# D3R900.net
KiCad netlist of a schematic drawn in Altium Designer
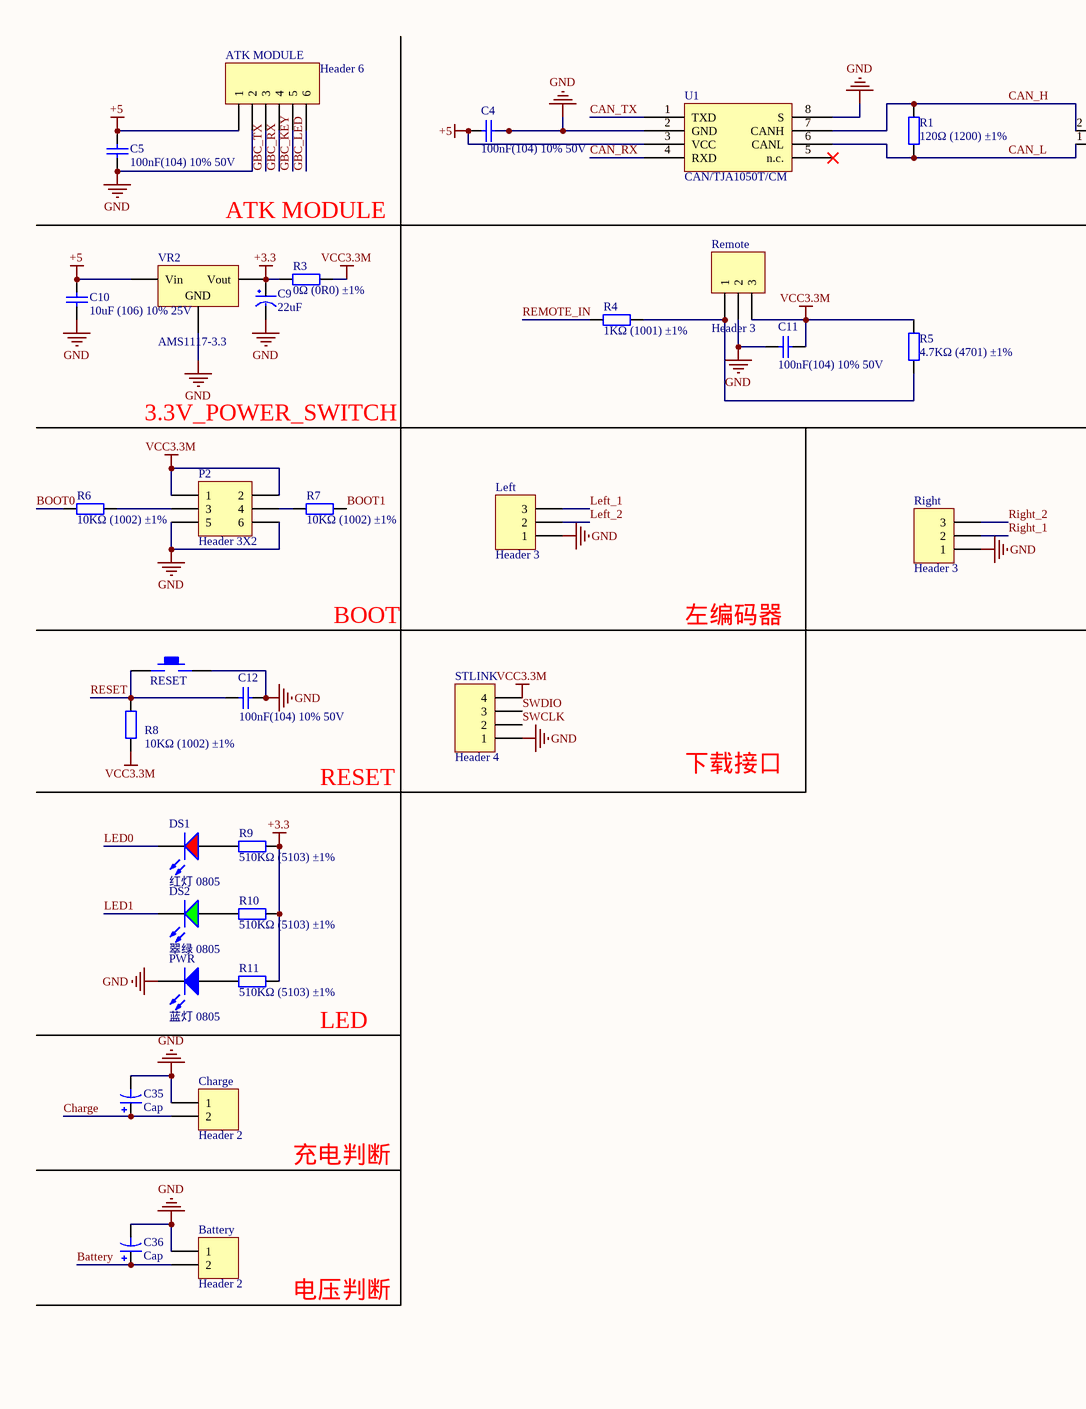
[diagram p0: D3R900.SchDoc, left]
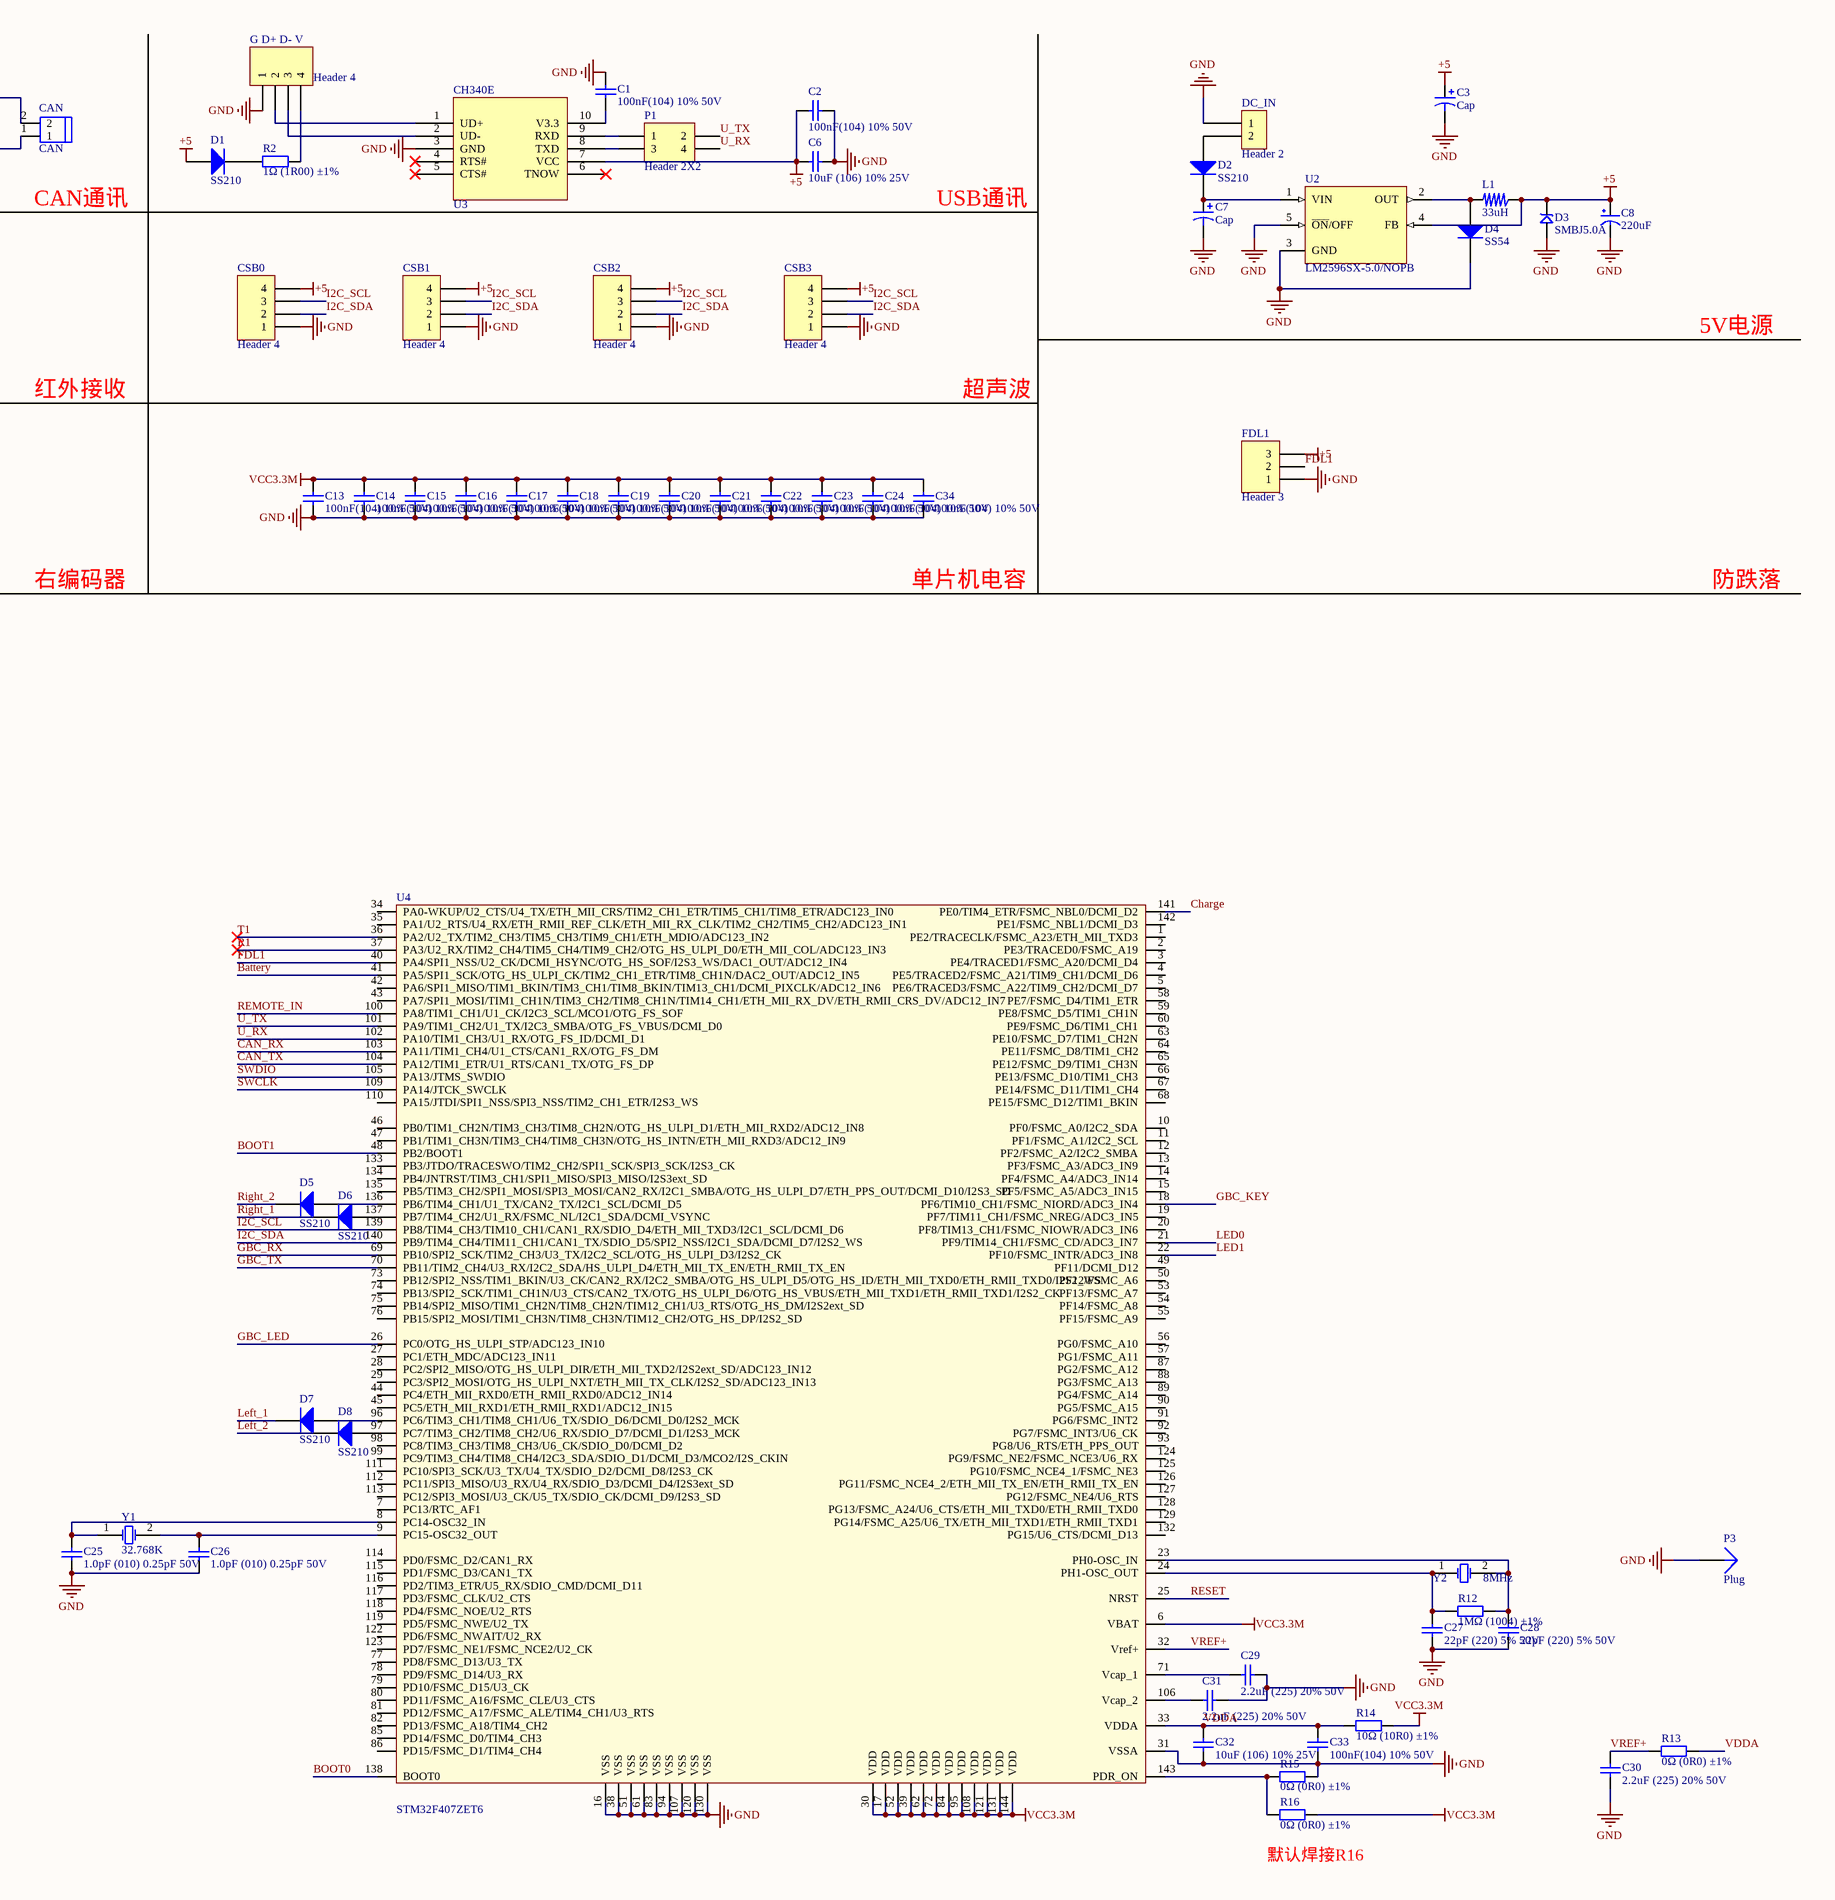
[diagram p1: D3R900.SchDoc, right]

(export (version "E")
  (design (tool "Eeschema 10.0.6"))
  (components
    (comp (ref "ATK MODULE")
      (value "Header 6")
      (footprint "HDR1X6")
      (description "Header, 6-Pin")
      (fields (field (name "PUBLISHER") "Altium Limited"))
      (libsource (lib "Miscellaneous Connectors") (part "Header 6"))
    )
    (comp (ref "Battery")
      (value "Header 2")
      (footprint "HDR1X2")
      (description "Header, 2-Pin")
      (fields (field (name "PUBLISHER") "Altium Limited"))
      (libsource (lib "Miscellaneous Connectors") (part "Header 2"))
    )
    (comp (ref "C1")
      (value "100nF(104) 10% 50V")
      (footprint "LC-0805_C")
      (description "贴片电容")
      (libsource (lib "Miscellaneous Devices LC") (part "0805 100nF(104) 10% 50V"))
    )
    (comp (ref "C2")
      (value "100nF(104) 10% 50V")
      (footprint "LC-0805_C")
      (description "贴片电容")
      (libsource (lib "Miscellaneous Devices LC") (part "0805 100nF(104) 10% 50V"))
    )
    (comp (ref "C3")
      (value "Cap")
      (footprint "CAP-DIP-3.5")
      (description "Cap_DIP")
      (libsource (lib "AD_Chip_Y") (part "Cap_DIP"))
    )
    (comp (ref "C4")
      (value "100nF(104) 10% 50V")
      (footprint "LC-0805_C")
      (description "贴片电容")
      (libsource (lib "Miscellaneous Devices LC") (part "0805 100nF(104) 10% 50V"))
    )
    (comp (ref "C5")
      (value "100nF(104) 10% 50V")
      (footprint "LC-0805_C")
      (description "贴片电容")
      (libsource (lib "Miscellaneous Devices LC") (part "0805 100nF(104) 10% 50V"))
    )
    (comp (ref "C6")
      (value "10uF (106) 10% 25V")
      (footprint "LC-0805_C")
      (description "贴片电容")
      (libsource (lib "Miscellaneous Devices LC") (part "0805 10uF (106) 10% 25V"))
    )
    (comp (ref "C7")
      (value "Cap")
      (footprint "CAP-DIP-3.5")
      (description "Cap_DIP")
      (libsource (lib "AD_Chip_Y") (part "Cap_DIP"))
    )
    (comp (ref "C8")
      (value "220uF")
      (footprint "CC6.56.5")
      (libsource (lib "Explorer STM32F407封装库") (part "CAP"))
    )
    (comp (ref "C9")
      (value "22uF")
      (footprint "CC6.56.5")
      (libsource (lib "Explorer STM32F407封装库") (part "CAP"))
    )
    (comp (ref "C10")
      (value "10uF (106) 10% 25V")
      (footprint "LC-0805_C")
      (description "贴片电容")
      (libsource (lib "Miscellaneous Devices LC") (part "0805 10uF (106) 10% 25V"))
    )
    (comp (ref "C11")
      (value "100nF(104) 10% 50V")
      (footprint "LC-0805_C")
      (description "贴片电容")
      (libsource (lib "Miscellaneous Devices LC") (part "0805 100nF(104) 10% 50V"))
    )
    (comp (ref "C12")
      (value "100nF(104) 10% 50V")
      (footprint "LC-0805_C")
      (description "贴片电容")
      (libsource (lib "Miscellaneous Devices LC") (part "0805 100nF(104) 10% 50V"))
    )
    (comp (ref "C13")
      (value "100nF(104) 10% 50V")
      (footprint "LC-0805_C")
      (description "贴片电容")
      (libsource (lib "Miscellaneous Devices LC") (part "0805 100nF(104) 10% 50V"))
    )
    (comp (ref "C14")
      (value "100nF(104) 10% 50V")
      (footprint "LC-0805_C")
      (description "贴片电容")
      (libsource (lib "Miscellaneous Devices LC") (part "0805 100nF(104) 10% 50V"))
    )
    (comp (ref "C15")
      (value "100nF(104) 10% 50V")
      (footprint "LC-0805_C")
      (description "贴片电容")
      (libsource (lib "Miscellaneous Devices LC") (part "0805 100nF(104) 10% 50V"))
    )
    (comp (ref "C16")
      (value "100nF(104) 10% 50V")
      (footprint "LC-0805_C")
      (description "贴片电容")
      (libsource (lib "Miscellaneous Devices LC") (part "0805 100nF(104) 10% 50V"))
    )
    (comp (ref "C17")
      (value "100nF(104) 10% 50V")
      (footprint "LC-0805_C")
      (description "贴片电容")
      (libsource (lib "Miscellaneous Devices LC") (part "0805 100nF(104) 10% 50V"))
    )
    (comp (ref "C18")
      (value "100nF(104) 10% 50V")
      (footprint "LC-0805_C")
      (description "贴片电容")
      (libsource (lib "Miscellaneous Devices LC") (part "0805 100nF(104) 10% 50V"))
    )
    (comp (ref "C19")
      (value "100nF(104) 10% 50V")
      (footprint "LC-0805_C")
      (description "贴片电容")
      (libsource (lib "Miscellaneous Devices LC") (part "0805 100nF(104) 10% 50V"))
    )
    (comp (ref "C20")
      (value "100nF(104) 10% 50V")
      (footprint "LC-0805_C")
      (description "贴片电容")
      (libsource (lib "Miscellaneous Devices LC") (part "0805 100nF(104) 10% 50V"))
    )
    (comp (ref "C21")
      (value "100nF(104) 10% 50V")
      (footprint "LC-0805_C")
      (description "贴片电容")
      (libsource (lib "Miscellaneous Devices LC") (part "0805 100nF(104) 10% 50V"))
    )
    (comp (ref "C22")
      (value "100nF(104) 10% 50V")
      (footprint "LC-0805_C")
      (description "贴片电容")
      (libsource (lib "Miscellaneous Devices LC") (part "0805 100nF(104) 10% 50V"))
    )
    (comp (ref "C23")
      (value "100nF(104) 10% 50V")
      (footprint "LC-0805_C")
      (description "贴片电容")
      (libsource (lib "Miscellaneous Devices LC") (part "0805 100nF(104) 10% 50V"))
    )
    (comp (ref "C24")
      (value "100nF(104) 10% 50V")
      (footprint "LC-0805_C")
      (description "贴片电容")
      (libsource (lib "Miscellaneous Devices LC") (part "0805 100nF(104) 10% 50V"))
    )
    (comp (ref "C25")
      (value "1.0pF (010) 0.25pF 50V")
      (footprint "LC-0805_C")
      (description "贴片电容")
      (libsource (lib "Miscellaneous Devices LC") (part "0805 1.0pF (010) 0.25pF 50V"))
    )
    (comp (ref "C26")
      (value "1.0pF (010) 0.25pF 50V")
      (footprint "LC-0805_C")
      (description "贴片电容")
      (libsource (lib "Miscellaneous Devices LC") (part "0805 1.0pF (010) 0.25pF 50V"))
    )
    (comp (ref "C27")
      (value "22pF (220) 5% 50V")
      (footprint "LC-0805_C")
      (description "贴片电容")
      (libsource (lib "Miscellaneous Devices LC") (part "0805 22pF (220) 5% 50V"))
    )
    (comp (ref "C28")
      (value "22pF (220) 5% 50V")
      (footprint "LC-0805_C")
      (description "贴片电容")
      (libsource (lib "Miscellaneous Devices LC") (part "0805 22pF (220) 5% 50V"))
    )
    (comp (ref "C29")
      (value "2.2uF (225) 20% 50V")
      (footprint "LC-0805_C")
      (description "贴片电容")
      (libsource (lib "Miscellaneous Devices LC") (part "0805 2.2uF (225) 20% 50V"))
    )
    (comp (ref "C30")
      (value "2.2uF (225) 20% 50V")
      (footprint "LC-0805_C")
      (description "贴片电容")
      (libsource (lib "Miscellaneous Devices LC") (part "0805 2.2uF (225) 20% 50V"))
    )
    (comp (ref "C31")
      (value "2.2uF (225) 20% 50V")
      (footprint "LC-0805_C")
      (description "贴片电容")
      (libsource (lib "Miscellaneous Devices LC") (part "0805 2.2uF (225) 20% 50V"))
    )
    (comp (ref "C32")
      (value "10uF (106) 10% 25V")
      (footprint "LC-0805_C")
      (description "贴片电容")
      (libsource (lib "Miscellaneous Devices LC") (part "0805 10uF (106) 10% 25V"))
    )
    (comp (ref "C33")
      (value "100nF(104) 10% 50V")
      (footprint "LC-0805_C")
      (description "贴片电容")
      (libsource (lib "Miscellaneous Devices LC") (part "0805 100nF(104) 10% 50V"))
    )
    (comp (ref "C34")
      (value "100nF(104) 10% 50V")
      (footprint "LC-0805_C")
      (description "贴片电容")
      (libsource (lib "Miscellaneous Devices LC") (part "0805 100nF(104) 10% 50V"))
    )
    (comp (ref "C35")
      (value "Cap")
      (footprint "CAP-DIP-3.5")
      (description "Cap_DIP")
      (libsource (lib "AD_Chip_Y") (part "Cap_DIP"))
    )
    (comp (ref "C36")
      (value "Cap")
      (footprint "CAP-DIP-3.5")
      (description "Cap_DIP")
      (libsource (lib "AD_Chip_Y") (part "Cap_DIP"))
    )
    (comp (ref "CAN")
      (value "CAN")
      (footprint "HEAD2L-0.8")
      (libsource (lib "Explorer STM32F407封装库") (part "HEAD2"))
    )
    (comp (ref "Charge")
      (value "Header 2")
      (footprint "HDR1X2")
      (description "Header, 2-Pin")
      (fields (field (name "PUBLISHER") "Altium Limited"))
      (libsource (lib "Miscellaneous Connectors") (part "Header 2"))
    )
    (comp (ref "CSB0")
      (value "Header 4")
      (footprint "HDR1X4")
      (description "Header, 4-Pin")
      (fields (field (name "PUBLISHER") "Altium Limited"))
      (libsource (lib "Miscellaneous Connectors") (part "Header 4"))
    )
    (comp (ref "CSB1")
      (value "Header 4")
      (footprint "HDR1X4")
      (description "Header, 4-Pin")
      (fields (field (name "PUBLISHER") "Altium Limited"))
      (libsource (lib "Miscellaneous Connectors") (part "Header 4"))
    )
    (comp (ref "CSB2")
      (value "Header 4")
      (footprint "HDR1X4")
      (description "Header, 4-Pin")
      (fields (field (name "PUBLISHER") "Altium Limited"))
      (libsource (lib "Miscellaneous Connectors") (part "Header 4"))
    )
    (comp (ref "CSB3")
      (value "Header 4")
      (footprint "HDR1X4")
      (description "Header, 4-Pin")
      (fields (field (name "PUBLISHER") "Altium Limited"))
      (libsource (lib "Miscellaneous Connectors") (part "Header 4"))
    )
    (comp (ref "D1")
      (value "SS210")
      (footprint "LC-SMA(DO-214AC)_S1")
      (description "二极管")
      (libsource (lib "Miscellaneous Devices LC") (part "SMA(DO-214AC) SS210"))
    )
    (comp (ref "D2")
      (value "SS210")
      (footprint "LC-SMA(DO-214AC)_S1")
      (description "二极管")
      (libsource (lib "Miscellaneous Devices LC") (part "SMA(DO-214AC) SS210"))
    )
    (comp (ref "D3")
      (value "SMBJ5.0A")
      (footprint "SMBJ")
      (description "TVS")
      (libsource (lib "Explorer STM32F407封装库") (part "SMBJ"))
    )
    (comp (ref "D4")
      (value "SS54")
      (footprint "LC-SMA(DO-214AC)_S1")
      (description "二极管")
      (libsource (lib "Miscellaneous Devices LC") (part "SMA(DO-214AC) SS54"))
    )
    (comp (ref "D5")
      (value "SS210")
      (footprint "LC-SMA(DO-214AC)_S1")
      (description "二极管")
      (libsource (lib "Miscellaneous Devices LC") (part "SMA(DO-214AC) SS210"))
    )
    (comp (ref "D6")
      (value "SS210")
      (footprint "LC-SMA(DO-214AC)_S1")
      (description "二极管")
      (libsource (lib "Miscellaneous Devices LC") (part "SMA(DO-214AC) SS210"))
    )
    (comp (ref "D7")
      (value "SS210")
      (footprint "LC-SMA(DO-214AC)_S1")
      (description "二极管")
      (libsource (lib "Miscellaneous Devices LC") (part "SMA(DO-214AC) SS210"))
    )
    (comp (ref "D8")
      (value "SS210")
      (footprint "LC-SMA(DO-214AC)_S1")
      (description "二极管")
      (libsource (lib "Miscellaneous Devices LC") (part "SMA(DO-214AC) SS210"))
    )
    (comp (ref "DC_IN")
      (value "Header 2")
      (footprint "VH-2A - Circle Hole")
      (description "贴片2p座")
      (libsource (lib "AD_Chip_Y") (part "Header 2"))
    )
    (comp (ref "DS1")
      (value "红灯 0805")
      (footprint "LC-0805_LED_S1")
      (description "发光二极管")
      (libsource (lib "Miscellaneous Devices LC") (part "0805 红灯"))
    )
    (comp (ref "DS2")
      (value "翠绿 0805")
      (footprint "LC-0805_LED_S1")
      (description "发光二极管")
      (libsource (lib "Miscellaneous Devices LC") (part "0805 翠绿"))
    )
    (comp (ref "FDL1")
      (value "Header 3")
      (footprint "HDR1X3")
      (description "Header, 3-Pin")
      (fields (field (name "PUBLISHER") "Altium Limited"))
      (libsource (lib "Miscellaneous Connectors") (part "Header 3"))
    )
    (comp (ref "G D+ D- V")
      (value "Header 4")
      (footprint "HDR1X4")
      (description "Header, 4-Pin")
      (fields (field (name "PUBLISHER") "Altium Limited"))
      (libsource (lib "") (part "Header 4_1"))
    )
    (comp (ref "L1")
      (value "33uH")
      (footprint "L_SOP74")
      (libsource (lib "Explorer STM32F407封装库") (part "L_SOP"))
    )
    (comp (ref "Left")
      (value "Header 3")
      (footprint "HDR1X3")
      (description "Header, 3-Pin")
      (fields (field (name "PUBLISHER") "Altium Limited"))
      (libsource (lib "Miscellaneous Connectors") (part "Header 3"))
    )
    (comp (ref "P1")
      (value "Header 2X2")
      (footprint "HDR2X2")
      (description "Header, 2-Pin, Dual row")
      (fields (field (name "PUBLISHER") "Altium Limited"))
      (libsource (lib "Miscellaneous Connectors") (part "Header 2X2"))
    )
    (comp (ref "P2")
      (value "Header 3X2")
      (footprint "HDR2X3")
      (description "Header, 3-Pin, Dual row")
      (fields (field (name "PUBLISHER") "Altium Limited"))
      (libsource (lib "Miscellaneous Connectors") (part "Header 3X2"))
    )
    (comp (ref "P3")
      (value "Plug")
      (footprint "PIN1")
      (fields (field (name "PUBLISHER") "Altium Limited"))
      (libsource (lib "Miscellaneous Connectors") (part "Plug"))
    )
    (comp (ref "PWR")
      (value "蓝灯 0805")
      (footprint "LC-0805_LED_S1")
      (description "发光二极管")
      (libsource (lib "Miscellaneous Devices LC") (part "0805 蓝灯"))
    )
    (comp (ref "R1")
      (value "120Ω (1200) ±1%")
      (footprint "LC-0805_R")
      (description "贴片电阻")
      (libsource (lib "Miscellaneous Devices LC") (part "0805 120Ω (1200) 1%"))
    )
    (comp (ref "R2")
      (value "1Ω (1R00) ±1%")
      (footprint "LC-0603_R")
      (description "贴片电阻")
      (libsource (lib "Miscellaneous Devices LC") (part "0603 1Ω (1R00) 1%"))
    )
    (comp (ref "R3")
      (value "0Ω (0R0) ±1%")
      (footprint "LC-0603_R")
      (description "贴片电阻")
      (libsource (lib "Miscellaneous Devices LC") (part "0603 0Ω (0R0) 1%"))
    )
    (comp (ref "R4")
      (value "1KΩ (1001) ±1%")
      (footprint "LC-0805_R")
      (description "贴片电阻")
      (libsource (lib "Miscellaneous Devices LC") (part "0805 1KΩ (1001) 1%"))
    )
    (comp (ref "R5")
      (value "4.7KΩ (4701) ±1%")
      (footprint "LC-0805_R")
      (description "贴片电阻")
      (libsource (lib "Miscellaneous Devices LC") (part "0805 4.7KΩ (4701) 1%"))
    )
    (comp (ref "R6")
      (value "10KΩ (1002) ±1%")
      (footprint "LC-0805_R")
      (description "贴片电阻")
      (libsource (lib "") (part "0805 10KΩ (1002) 1%_1"))
    )
    (comp (ref "R7")
      (value "10KΩ (1002) ±1%")
      (footprint "LC-0805_R")
      (description "贴片电阻")
      (libsource (lib "") (part "0805 10KΩ (1002) 1%_1"))
    )
    (comp (ref "R8")
      (value "10KΩ (1002) ±1%")
      (footprint "LC-0805_R")
      (description "贴片电阻")
      (libsource (lib "Miscellaneous Devices LC") (part "0805 10KΩ (1002) 1%"))
    )
    (comp (ref "R9")
      (value "510KΩ (5103) ±1%")
      (footprint "LC-0805_R")
      (description "贴片电阻")
      (libsource (lib "Miscellaneous Devices LC") (part "0805 510KΩ (5103) 1%"))
    )
    (comp (ref "R10")
      (value "510KΩ (5103) ±1%")
      (footprint "LC-0805_R")
      (description "贴片电阻")
      (libsource (lib "Miscellaneous Devices LC") (part "0805 510KΩ (5103) 1%"))
    )
    (comp (ref "R11")
      (value "510KΩ (5103) ±1%")
      (footprint "LC-0805_R")
      (description "贴片电阻")
      (libsource (lib "Miscellaneous Devices LC") (part "0805 510KΩ (5103) 1%"))
    )
    (comp (ref "R12")
      (value "1MΩ (1004) ±1%")
      (footprint "LC-0805_R")
      (description "贴片电阻")
      (libsource (lib "Miscellaneous Devices LC") (part "0805 1MΩ (1004) 1%"))
    )
    (comp (ref "R13")
      (value "0Ω (0R0) ±1%")
      (footprint "LC-0603_R")
      (description "贴片电阻")
      (libsource (lib "Miscellaneous Devices LC") (part "0603 0Ω (0R0) 1%"))
    )
    (comp (ref "R14")
      (value "10Ω (10R0) ±1%")
      (footprint "LC-0805_R")
      (description "贴片电阻")
      (libsource (lib "Miscellaneous Devices LC") (part "0805 10Ω (10R0) 1%"))
    )
    (comp (ref "R15")
      (value "0Ω (0R0) ±1%")
      (footprint "LC-0603_R")
      (description "贴片电阻")
      (libsource (lib "Miscellaneous Devices LC") (part "0603 0Ω (0R0) 1%"))
    )
    (comp (ref "R16")
      (value "0Ω (0R0) ±1%")
      (footprint "LC-0603_R")
      (description "贴片电阻")
      (libsource (lib "Miscellaneous Devices LC") (part "0603 0Ω (0R0) 1%"))
    )
    (comp (ref "Remote")
      (value "Header 3")
      (footprint "HDR1X3")
      (description "Header, 3-Pin")
      (fields (field (name "PUBLISHER") "Altium Limited"))
      (libsource (lib "") (part "Header 3_1"))
    )
    (comp (ref "RESET")
      (value "KEY_M")
      (footprint "KEY_M")
      (libsource (lib "Explorer STM32F407封装库") (part "KEY_M"))
    )
    (comp (ref "Right")
      (value "Header 3")
      (footprint "HDR1X3")
      (description "Header, 3-Pin")
      (fields (field (name "PUBLISHER") "Altium Limited"))
      (libsource (lib "Miscellaneous Connectors") (part "Header 3"))
    )
    (comp (ref "STLINK")
      (value "Header 4")
      (footprint "HDR1X4")
      (description "Header, 4-Pin")
      (fields (field (name "PUBLISHER") "Altium Limited"))
      (libsource (lib "Miscellaneous Connectors") (part "Header 4"))
    )
    (comp (ref "U1")
      (value "CAN/TJA1050T/CM")
      (footprint "LC-SOIC-8_150mil")
      (description "CAN")
      (libsource (lib "Miscellaneous Devices LC") (part "CAN/TJA1050T/CM"))
    )
    (comp (ref "U2")
      (value "LM2596SX-5.0/NOPB")
      (footprint "LC-TO-263-5")
      (description "DC-DC芯片")
      (libsource (lib "Miscellaneous Devices LC") (part "LM2596SX-5.0/NOPB"))
    )
    (comp (ref "U3")
      (value "CH340E")
      (footprint "LC-MSOP-10")
      (description "USB")
      (libsource (lib "AD_Chip_Y") (part "CH340E"))
    )
    (comp (ref "U4")
      (value "STM32F407ZET6")
      (footprint "LQFP144")
      (libsource (lib "Explorer STM32F407封装库") (part "STM32F407ZET6"))
    )
    (comp (ref "VR2")
      (value "AMS1117-3.3")
      (footprint "LC-SOT-223")
      (description "低压差线性稳压(LDO)")
      (libsource (lib "Miscellaneous Devices LC") (part "SOT-223 AMS1117-3.3"))
    )
    (comp (ref "Y1")
      (value "32.768K")
      (footprint "R38")
      (description "Crystal Oscillator")
      (fields (field (name "PUBLISHER") "Altium Limited"))
      (libsource (lib "Miscellaneous Devices") (part "XTAL"))
    )
    (comp (ref "Y2")
      (value "8MHz")
      (footprint "XTAL_US")
      (description "Crystal Oscillator")
      (fields (field (name "PUBLISHER") "Altium Limited"))
      (libsource (lib "Explorer STM32F407封装库") (part "XTAL"))
    )
  )
  (nets
    (net (code "1") (name "+3.3") (class "Default")
      (node (ref "C9") (pin "1") (pinfunction "VCC_1") (pintype "passive"))
      (node (ref "R10") (pin "2") (pinfunction "2_2") (pintype "passive"))
      (node (ref "R11") (pin "2") (pinfunction "2_2") (pintype "passive"))
      (node (ref "R3") (pin "1") (pinfunction "1_1") (pintype "passive"))
      (node (ref "R9") (pin "2") (pinfunction "2_2") (pintype "passive"))
      (node (ref "VR2") (pin "2") (pinfunction "Vout_2") (pintype "passive"))
    )
    (net (code "2") (name "+5") (class "Default")
      (node (ref "ATK MODULE") (pin "1") (pinfunction "1_1") (pintype "passive"))
      (node (ref "C10") (pin "2") (pinfunction "2_2") (pintype "passive"))
      (node (ref "C2") (pin "1") (pinfunction "1_1") (pintype "passive"))
      (node (ref "C3") (pin "1") (pinfunction "1_1") (pintype "passive"))
      (node (ref "C4") (pin "1") (pinfunction "1_1") (pintype "passive"))
      (node (ref "C5") (pin "2") (pinfunction "2_2") (pintype "passive"))
      (node (ref "C6") (pin "1") (pinfunction "1_1") (pintype "passive"))
      (node (ref "C8") (pin "1") (pinfunction "VCC_1") (pintype "passive"))
      (node (ref "CSB0") (pin "4") (pinfunction "4_4") (pintype "passive"))
      (node (ref "CSB1") (pin "4") (pinfunction "4_4") (pintype "passive"))
      (node (ref "CSB2") (pin "4") (pinfunction "4_4") (pintype "passive"))
      (node (ref "CSB3") (pin "4") (pinfunction "4_4") (pintype "passive"))
      (node (ref "D1") (pin "1") (pinfunction "A_1") (pintype "passive"))
      (node (ref "D3") (pin "2") (pintype "passive"))
      (node (ref "FDL1") (pin "3") (pinfunction "3_3") (pintype "passive"))
      (node (ref "L1") (pin "1") (pinfunction "1_1") (pintype "passive"))
      (node (ref "U1") (pin "3") (pinfunction "VCC_3") (pintype "passive"))
      (node (ref "U2") (pin "4") (pinfunction "FB_4") (pintype "input"))
      (node (ref "U3") (pin "7") (pinfunction "VCC_7") (pintype "passive"))
      (node (ref "VR2") (pin "3") (pinfunction "Vin_3") (pintype "passive"))
    )
    (net (code "3") (name "/BOOT0") (class "Default")
      (node (ref "R6") (pin "1") (pinfunction "1_1") (pintype "passive"))
      (node (ref "U4") (pin "138") (pinfunction "BOOT0_138") (pintype "passive"))
    )
    (net (code "4") (name "/BOOT1") (class "Default")
      (node (ref "R7") (pin "2") (pinfunction "2_2") (pintype "passive"))
      (node (ref "U4") (pin "48") (pinfunction "PB2/BOOT1_48") (pintype "passive"))
    )
    (net (code "5") (name "/Battery") (class "Default")
      (node (ref "Battery") (pin "2") (pinfunction "2_2") (pintype "passive"))
      (node (ref "C36") (pin "1") (pinfunction "1_1") (pintype "passive"))
      (node (ref "U4") (pin "41") (pinfunction "PA5/SPI1_SCK/OTG_HS_ULPI_CK/TIM2_CH1_ETR/TIM8_CH1N/DAC2_OUT/ADC12_IN5_41") (pintype "passive"))
    )
    (net (code "6") (name "/CAN_H") (class "Default")
      (node (ref "CAN") (pin "2") (pinfunction "2_2") (pintype "passive"))
      (node (ref "R1") (pin "2") (pinfunction "2_2") (pintype "passive"))
      (node (ref "U1") (pin "7") (pinfunction "CANH_7") (pintype "passive"))
    )
    (net (code "7") (name "/CAN_L") (class "Default")
      (node (ref "CAN") (pin "1") (pinfunction "1_1") (pintype "passive"))
      (node (ref "R1") (pin "1") (pinfunction "1_1") (pintype "passive"))
      (node (ref "U1") (pin "6") (pinfunction "CANL_6") (pintype "passive"))
    )
    (net (code "8") (name "/CAN_RX") (class "Default")
      (node (ref "U1") (pin "4") (pinfunction "RXD_4") (pintype "passive"))
      (node (ref "U4") (pin "103") (pinfunction "PA11/TIM1_CH4/U1_CTS/CAN1_RX/OTG_FS_DM_103") (pintype "passive"))
    )
    (net (code "9") (name "/CAN_TX") (class "Default")
      (node (ref "U1") (pin "1") (pinfunction "TXD_1") (pintype "passive"))
      (node (ref "U4") (pin "104") (pinfunction "PA12/TIM1_ETR/U1_RTS/CAN1_TX/OTG_FS_DP_104") (pintype "passive"))
    )
    (net (code "10") (name "/Charge") (class "Default")
      (node (ref "C35") (pin "1") (pinfunction "1_1") (pintype "passive"))
      (node (ref "Charge") (pin "2") (pinfunction "2_2") (pintype "passive"))
      (node (ref "U4") (pin "141") (pinfunction "PE0/TIM4_ETR/FSMC_NBL0/DCMI_D2_141") (pintype "passive"))
    )
    (net (code "11") (name "/FDL1") (class "Default")
      (node (ref "FDL1") (pin "2") (pinfunction "2_2") (pintype "passive"))
      (node (ref "U4") (pin "40") (pinfunction "PA4/SPI1_NSS/U2_CK/DCMI_HSYNC/OTG_HS_SOF/I2S3_WS/DAC1_OUT/ADC12_IN4_40") (pintype "passive"))
    )
    (net (code "12") (name "/GBC_KEY") (class "Default")
      (node (ref "ATK MODULE") (pin "5") (pinfunction "5_5") (pintype "passive"))
      (node (ref "U4") (pin "18") (pinfunction "PF6/TIM10_CH1/FSMC_NIORD/ADC3_IN4_18") (pintype "passive"))
    )
    (net (code "13") (name "/GBC_LED") (class "Default")
      (node (ref "ATK MODULE") (pin "6") (pinfunction "6_6") (pintype "passive"))
      (node (ref "U4") (pin "26") (pinfunction "PC0/OTG_HS_ULPI_STP/ADC123_IN10_26") (pintype "passive"))
    )
    (net (code "14") (name "/GBC_RX") (class "Default")
      (node (ref "ATK MODULE") (pin "4") (pinfunction "4_4") (pintype "passive"))
      (node (ref "U4") (pin "69") (pinfunction "PB10/SPI2_SCK/TIM2_CH3/U3_TX/I2C2_SCL/OTG_HS_ULPI_D3/I2S2_CK_69") (pintype "passive"))
    )
    (net (code "15") (name "/GBC_TX") (class "Default")
      (node (ref "ATK MODULE") (pin "3") (pinfunction "3_3") (pintype "passive"))
      (node (ref "U4") (pin "70") (pinfunction "PB11/TIM2_CH4/U3_RX/I2C2_SDA/HS_ULPI_D4/ETH_MII_TX_EN/ETH_RMII_TX_EN_70") (pintype "passive"))
    )
    (net (code "16") (name "/I2C_SCL") (class "Default")
      (node (ref "CSB0") (pin "3") (pinfunction "3_3") (pintype "passive"))
      (node (ref "CSB1") (pin "3") (pinfunction "3_3") (pintype "passive"))
      (node (ref "CSB2") (pin "3") (pinfunction "3_3") (pintype "passive"))
      (node (ref "CSB3") (pin "3") (pinfunction "3_3") (pintype "passive"))
      (node (ref "U4") (pin "139") (pinfunction "PB8/TIM4_CH3/TIM10_CH1/CAN1_RX/SDIO_D4/ETH_MII_TXD3/I2C1_SCL/DCMI_D6_139") (pintype "passive"))
    )
    (net (code "17") (name "/I2C_SDA") (class "Default")
      (node (ref "CSB0") (pin "2") (pinfunction "2_2") (pintype "passive"))
      (node (ref "CSB1") (pin "2") (pinfunction "2_2") (pintype "passive"))
      (node (ref "CSB2") (pin "2") (pinfunction "2_2") (pintype "passive"))
      (node (ref "CSB3") (pin "2") (pinfunction "2_2") (pintype "passive"))
      (node (ref "U4") (pin "140") (pinfunction "PB9/TIM4_CH4/TIM11_CH1/CAN1_TX/SDIO_D5/SPI2_NSS/I2C1_SDA/DCMI_D7/I2S2_WS_140") (pintype "passive"))
    )
    (net (code "18") (name "/LED0") (class "Default")
      (node (ref "DS1") (pin "K") (pinfunction "K_K") (pintype "passive"))
      (node (ref "U4") (pin "21") (pinfunction "PF9/TIM14_CH1/FSMC_CD/ADC3_IN7_21") (pintype "passive"))
    )
    (net (code "19") (name "/LED1") (class "Default")
      (node (ref "DS2") (pin "K") (pinfunction "K_K") (pintype "passive"))
      (node (ref "U4") (pin "22") (pinfunction "PF10/FSMC_INTR/ADC3_IN8_22") (pintype "passive"))
    )
    (net (code "20") (name "/Left_1") (class "Default")
      (node (ref "D7") (pin "2") (pinfunction "K_2") (pintype "passive"))
      (node (ref "Left") (pin "3") (pinfunction "3_3") (pintype "passive"))
    )
    (net (code "21") (name "/Left_2") (class "Default")
      (node (ref "D8") (pin "2") (pinfunction "K_2") (pintype "passive"))
      (node (ref "Left") (pin "2") (pinfunction "2_2") (pintype "passive"))
    )
    (net (code "22") (name "/R1") (class "Default")
      (node (ref "U4") (pin "37") (pinfunction "PA3/U2_RX/TIM2_CH4/TIM5_CH4/TIM9_CH2/OTG_HS_ULPI_D0/ETH_MII_COL/ADC123_IN3_37") (pintype "passive+no_connect"))
    )
    (net (code "23") (name "/REMOTE_IN") (class "Default")
      (node (ref "R4") (pin "1") (pinfunction "1_1") (pintype "passive"))
      (node (ref "U4") (pin "100") (pinfunction "PA8/TIM1_CH1/U1_CK/I2C3_SCL/MCO1/OTG_FS_SOF_100") (pintype "passive"))
    )
    (net (code "24") (name "/RESET") (class "Default")
      (node (ref "C12") (pin "2") (pinfunction "2_2") (pintype "passive"))
      (node (ref "R8") (pin "2") (pinfunction "2_2") (pintype "passive"))
      (node (ref "RESET") (pin "1") (pinfunction "1_1") (pintype "passive"))
      (node (ref "U4") (pin "25") (pinfunction "NRST_25") (pintype "passive"))
    )
    (net (code "25") (name "/Right_1") (class "Default")
      (node (ref "D6") (pin "2") (pinfunction "K_2") (pintype "passive"))
      (node (ref "Right") (pin "2") (pinfunction "2_2") (pintype "passive"))
    )
    (net (code "26") (name "/Right_2") (class "Default")
      (node (ref "D5") (pin "2") (pinfunction "K_2") (pintype "passive"))
      (node (ref "Right") (pin "3") (pinfunction "3_3") (pintype "passive"))
    )
    (net (code "27") (name "/SWCLK") (class "Default")
      (node (ref "STLINK") (pin "2") (pinfunction "2_2") (pintype "passive"))
      (node (ref "U4") (pin "109") (pinfunction "PA14/JTCK_SWCLK_109") (pintype "passive"))
    )
    (net (code "28") (name "/SWDIO") (class "Default")
      (node (ref "STLINK") (pin "3") (pinfunction "3_3") (pintype "passive"))
      (node (ref "U4") (pin "105") (pinfunction "PA13/JTMS_SWDIO_105") (pintype "passive"))
    )
    (net (code "29") (name "/T1") (class "Default")
      (node (ref "U4") (pin "36") (pinfunction "PA2/U2_TX/TIM2_CH3/TIM5_CH3/TIM9_CH1/ETH_MDIO/ADC123_IN2_36") (pintype "passive+no_connect"))
    )
    (net (code "30") (name "/U_RX") (class "Default")
      (node (ref "P1") (pin "4") (pinfunction "4_4") (pintype "passive"))
      (node (ref "U4") (pin "102") (pinfunction "PA10/TIM1_CH3/U1_RX/OTG_FS_ID/DCMI_D1_102") (pintype "passive"))
    )
    (net (code "31") (name "/U_TX") (class "Default")
      (node (ref "P1") (pin "2") (pinfunction "2_2") (pintype "passive"))
      (node (ref "U4") (pin "101") (pinfunction "PA9/TIM1_CH2/U1_TX/I2C3_SMBA/OTG_FS_VBUS/DCMI_D0_101") (pintype "passive"))
    )
    (net (code "32") (name "/VDDA") (class "Default")
      (node (ref "C32") (pin "2") (pinfunction "2_2") (pintype "passive"))
      (node (ref "C33") (pin "2") (pinfunction "2_2") (pintype "passive"))
      (node (ref "R13") (pin "2") (pinfunction "2_2") (pintype "passive"))
      (node (ref "R14") (pin "1") (pinfunction "1_1") (pintype "passive"))
      (node (ref "U4") (pin "33") (pinfunction "VDDA_33") (pintype "passive"))
    )
    (net (code "33") (name "/VREF+") (class "Default")
      (node (ref "C30") (pin "2") (pinfunction "2_2") (pintype "passive"))
      (node (ref "R13") (pin "1") (pinfunction "1_1") (pintype "passive"))
      (node (ref "U4") (pin "32") (pinfunction "Vref+_32") (pintype "passive"))
    )
    (net (code "34") (name "GND") (class "Default")
      (node (ref "ATK MODULE") (pin "2") (pinfunction "2_2") (pintype "passive"))
      (node (ref "Battery") (pin "1") (pinfunction "1_1") (pintype "passive"))
      (node (ref "C1") (pin "2") (pinfunction "2_2") (pintype "passive"))
      (node (ref "C10") (pin "1") (pinfunction "1_1") (pintype "passive"))
      (node (ref "C11") (pin "1") (pinfunction "1_1") (pintype "passive"))
      (node (ref "C12") (pin "1") (pinfunction "1_1") (pintype "passive"))
      (node (ref "C13") (pin "2") (pinfunction "2_2") (pintype "passive"))
      (node (ref "C14") (pin "2") (pinfunction "2_2") (pintype "passive"))
      (node (ref "C15") (pin "2") (pinfunction "2_2") (pintype "passive"))
      (node (ref "C16") (pin "2") (pinfunction "2_2") (pintype "passive"))
      (node (ref "C17") (pin "2") (pinfunction "2_2") (pintype "passive"))
      (node (ref "C18") (pin "2") (pinfunction "2_2") (pintype "passive"))
      (node (ref "C19") (pin "2") (pinfunction "2_2") (pintype "passive"))
      (node (ref "C2") (pin "2") (pinfunction "2_2") (pintype "passive"))
      (node (ref "C20") (pin "2") (pinfunction "2_2") (pintype "passive"))
      (node (ref "C21") (pin "2") (pinfunction "2_2") (pintype "passive"))
      (node (ref "C22") (pin "2") (pinfunction "2_2") (pintype "passive"))
      (node (ref "C23") (pin "2") (pinfunction "2_2") (pintype "passive"))
      (node (ref "C24") (pin "2") (pinfunction "2_2") (pintype "passive"))
      (node (ref "C25") (pin "1") (pinfunction "1_1") (pintype "passive"))
      (node (ref "C26") (pin "1") (pinfunction "1_1") (pintype "passive"))
      (node (ref "C27") (pin "1") (pinfunction "1_1") (pintype "passive"))
      (node (ref "C28") (pin "1") (pinfunction "1_1") (pintype "passive"))
      (node (ref "C29") (pin "2") (pinfunction "2_2") (pintype "passive"))
      (node (ref "C3") (pin "2") (pinfunction "2_2") (pintype "passive"))
      (node (ref "C30") (pin "1") (pinfunction "1_1") (pintype "passive"))
      (node (ref "C31") (pin "2") (pinfunction "2_2") (pintype "passive"))
      (node (ref "C32") (pin "1") (pinfunction "1_1") (pintype "passive"))
      (node (ref "C33") (pin "1") (pinfunction "1_1") (pintype "passive"))
      (node (ref "C34") (pin "2") (pinfunction "2_2") (pintype "passive"))
      (node (ref "C35") (pin "2") (pinfunction "2_2") (pintype "passive"))
      (node (ref "C36") (pin "2") (pinfunction "2_2") (pintype "passive"))
      (node (ref "C4") (pin "2") (pinfunction "2_2") (pintype "passive"))
      (node (ref "C5") (pin "1") (pinfunction "1_1") (pintype "passive"))
      (node (ref "C6") (pin "2") (pinfunction "2_2") (pintype "passive"))
      (node (ref "C7") (pin "2") (pinfunction "2_2") (pintype "passive"))
      (node (ref "C8") (pin "2") (pinfunction "GND_2") (pintype "passive"))
      (node (ref "C9") (pin "2") (pinfunction "GND_2") (pintype "passive"))
      (node (ref "CSB0") (pin "1") (pinfunction "1_1") (pintype "passive"))
      (node (ref "CSB1") (pin "1") (pinfunction "1_1") (pintype "passive"))
      (node (ref "CSB2") (pin "1") (pinfunction "1_1") (pintype "passive"))
      (node (ref "CSB3") (pin "1") (pinfunction "1_1") (pintype "passive"))
      (node (ref "Charge") (pin "1") (pinfunction "1_1") (pintype "passive"))
      (node (ref "D3") (pin "1") (pintype "passive"))
      (node (ref "D4") (pin "2") (pinfunction "K_2") (pintype "passive"))
      (node (ref "DC_IN") (pin "1") (pinfunction "1_1") (pintype "passive"))
      (node (ref "FDL1") (pin "1") (pinfunction "1_1") (pintype "passive"))
      (node (ref "G D+ D- V") (pin "1") (pinfunction "1_1") (pintype "passive"))
      (node (ref "Left") (pin "1") (pinfunction "1_1") (pintype "passive"))
      (node (ref "P2") (pin "5") (pinfunction "5_5") (pintype "passive"))
      (node (ref "P2") (pin "6") (pinfunction "6_6") (pintype "passive"))
      (node (ref "P3") (pin "1") (pinfunction "1_1") (pintype "passive"))
      (node (ref "PWR") (pin "K") (pinfunction "K_K") (pintype "passive"))
      (node (ref "R15") (pin "2") (pinfunction "2_2") (pintype "passive"))
      (node (ref "RESET") (pin "2") (pinfunction "2_2") (pintype "passive"))
      (node (ref "Remote") (pin "2") (pinfunction "2_2") (pintype "passive"))
      (node (ref "Right") (pin "1") (pinfunction "1_1") (pintype "passive"))
      (node (ref "STLINK") (pin "1") (pinfunction "1_1") (pintype "passive"))
      (node (ref "U1") (pin "2") (pinfunction "GND_2") (pintype "passive"))
      (node (ref "U1") (pin "8") (pinfunction "S_8") (pintype "passive"))
      (node (ref "U2") (pin "3") (pinfunction "GND_3") (pintype "power_in"))
      (node (ref "U2") (pin "5") (pinfunction "~{ON}/OFF_5") (pintype "input"))
      (node (ref "U3") (pin "3") (pinfunction "GND_3") (pintype "passive"))
      (node (ref "U4") (pin "107") (pinfunction "VSS_107") (pintype "passive"))
      (node (ref "U4") (pin "120") (pinfunction "VSS_120") (pintype "passive"))
      (node (ref "U4") (pin "130") (pinfunction "VSS_130") (pintype "passive"))
      (node (ref "U4") (pin "16") (pinfunction "VSS_16") (pintype "passive"))
      (node (ref "U4") (pin "31") (pinfunction "VSSA_31") (pintype "passive"))
      (node (ref "U4") (pin "38") (pinfunction "VSS_38") (pintype "passive"))
      (node (ref "U4") (pin "51") (pinfunction "VSS_51") (pintype "passive"))
      (node (ref "U4") (pin "61") (pinfunction "VSS_61") (pintype "passive"))
      (node (ref "U4") (pin "83") (pinfunction "VSS_83") (pintype "passive"))
      (node (ref "U4") (pin "94") (pinfunction "VSS_94") (pintype "passive"))
      (node (ref "VR2") (pin "1") (pinfunction "GND_1") (pintype "passive"))
    )
    (net (code "35") (name "Net-(D1-K)") (class "Default")
      (node (ref "D1") (pin "2") (pinfunction "K_2") (pintype "passive"))
      (node (ref "R2") (pin "1") (pinfunction "1_1") (pintype "passive"))
    )
    (net (code "36") (name "Net-(D2-A)") (class "Default")
      (node (ref "D2") (pin "1") (pinfunction "A_1") (pintype "passive"))
      (node (ref "DC_IN") (pin "2") (pinfunction "2_2") (pintype "passive"))
    )
    (net (code "37") (name "Net-(D2-K)") (class "Default")
      (node (ref "C7") (pin "1") (pinfunction "1_1") (pintype "passive"))
      (node (ref "D2") (pin "2") (pinfunction "K_2") (pintype "passive"))
      (node (ref "U2") (pin "1") (pinfunction "VIN_1") (pintype "input"))
    )
    (net (code "38") (name "Net-(D4-A)") (class "Default")
      (node (ref "D4") (pin "1") (pinfunction "A_1") (pintype "passive"))
      (node (ref "L1") (pin "2") (pinfunction "2_2") (pintype "passive"))
      (node (ref "U2") (pin "2") (pinfunction "OUT_2") (pintype "output"))
    )
    (net (code "39") (name "Net-(D5-A)") (class "Default")
      (node (ref "D5") (pin "1") (pinfunction "A_1") (pintype "passive"))
      (node (ref "U4") (pin "136") (pinfunction "PB6/TIM4_CH1/U1_TX/CAN2_TX/I2C1_SCL/DCMI_D5_136") (pintype "passive"))
    )
    (net (code "40") (name "Net-(D6-A)") (class "Default")
      (node (ref "D6") (pin "1") (pinfunction "A_1") (pintype "passive"))
      (node (ref "U4") (pin "137") (pinfunction "PB7/TIM4_CH2/U1_RX/FSMC_NL/I2C1_SDA/DCMI_VSYNC_137") (pintype "passive"))
    )
    (net (code "41") (name "Net-(D7-A)") (class "Default")
      (node (ref "D7") (pin "1") (pinfunction "A_1") (pintype "passive"))
      (node (ref "U4") (pin "96") (pinfunction "PC6/TIM3_CH1/TIM8_CH1/U6_TX/SDIO_D6/DCMI_D0/I2S2_MCK_96") (pintype "passive"))
    )
    (net (code "42") (name "Net-(D8-A)") (class "Default")
      (node (ref "D8") (pin "1") (pinfunction "A_1") (pintype "passive"))
      (node (ref "U4") (pin "97") (pinfunction "PC7/TIM3_CH2/TIM8_CH2/U6_RX/SDIO_D7/DCMI_D1/I2S3_MCK_97") (pintype "passive"))
    )
    (net (code "43") (name "Net-(DS1-PadA)") (class "Default")
      (node (ref "DS1") (pin "A") (pinfunction "A_A") (pintype "passive"))
      (node (ref "R9") (pin "1") (pinfunction "1_1") (pintype "passive"))
    )
    (net (code "44") (name "Net-(DS2-PadA)") (class "Default")
      (node (ref "DS2") (pin "A") (pinfunction "A_A") (pintype "passive"))
      (node (ref "R10") (pin "1") (pinfunction "1_1") (pintype "passive"))
    )
    (net (code "45") (name "Net-(G D+ D- V-Pad4)") (class "Default")
      (node (ref "G D+ D- V") (pin "4") (pinfunction "4_4") (pintype "passive"))
      (node (ref "R2") (pin "2") (pinfunction "2_2") (pintype "passive"))
    )
    (net (code "46") (name "Net-(P2-Pad3)") (class "Default")
      (node (ref "P2") (pin "3") (pinfunction "3_3") (pintype "passive"))
      (node (ref "R6") (pin "2") (pinfunction "2_2") (pintype "passive"))
    )
    (net (code "47") (name "Net-(P2-Pad4)") (class "Default")
      (node (ref "P2") (pin "4") (pinfunction "4_4") (pintype "passive"))
      (node (ref "R7") (pin "1") (pinfunction "1_1") (pintype "passive"))
    )
    (net (code "48") (name "Net-(PWR-PadA)") (class "Default")
      (node (ref "PWR") (pin "A") (pinfunction "A_A") (pintype "passive"))
      (node (ref "R11") (pin "1") (pinfunction "1_1") (pintype "passive"))
    )
    (net (code "49") (name "Net-(R4-Pad2)") (class "Default")
      (node (ref "R4") (pin "2") (pinfunction "2_2") (pintype "passive"))
      (node (ref "R5") (pin "1") (pinfunction "1_1") (pintype "passive"))
      (node (ref "Remote") (pin "1") (pinfunction "1_1") (pintype "passive"))
    )
    (net (code "50") (name "Net-(U3-RXD)") (class "Default")
      (node (ref "P1") (pin "1") (pinfunction "1_1") (pintype "passive"))
      (node (ref "U3") (pin "9") (pinfunction "RXD_9") (pintype "passive"))
    )
    (net (code "51") (name "Net-(U3-TXD)") (class "Default")
      (node (ref "P1") (pin "3") (pinfunction "3_3") (pintype "passive"))
      (node (ref "U3") (pin "8") (pinfunction "TXD_8") (pintype "passive"))
    )
    (net (code "52") (name "Net-(U3-UD+)") (class "Default")
      (node (ref "G D+ D- V") (pin "2") (pinfunction "2_2") (pintype "passive"))
      (node (ref "U3") (pin "1") (pinfunction "UD+_1") (pintype "passive"))
    )
    (net (code "53") (name "Net-(U3-UD-)") (class "Default")
      (node (ref "G D+ D- V") (pin "3") (pinfunction "3_3") (pintype "passive"))
      (node (ref "U3") (pin "2") (pinfunction "UD-_2") (pintype "passive"))
    )
    (net (code "54") (name "Net-(U3-V3.3)") (class "Default")
      (node (ref "C1") (pin "1") (pinfunction "1_1") (pintype "passive"))
      (node (ref "U3") (pin "10") (pinfunction "V3.3_10") (pintype "passive"))
    )
    (net (code "55") (name "Net-(U4-PC14-OSC32_IN)") (class "Default")
      (node (ref "C25") (pin "2") (pinfunction "2_2") (pintype "passive"))
      (node (ref "U4") (pin "8") (pinfunction "PC14-OSC32_IN_8") (pintype "passive"))
      (node (ref "Y1") (pin "1") (pinfunction "OSC1_1") (pintype "passive"))
    )
    (net (code "56") (name "Net-(U4-PC15-OSC32_OUT)") (class "Default")
      (node (ref "C26") (pin "2") (pinfunction "2_2") (pintype "passive"))
      (node (ref "U4") (pin "9") (pinfunction "PC15-OSC32_OUT_9") (pintype "passive"))
      (node (ref "Y1") (pin "2") (pinfunction "OSC2_2") (pintype "passive"))
    )
    (net (code "57") (name "Net-(U4-PDR_ON)") (class "Default")
      (node (ref "R15") (pin "1") (pinfunction "1_1") (pintype "passive"))
      (node (ref "R16") (pin "1") (pinfunction "1_1") (pintype "passive"))
      (node (ref "U4") (pin "143") (pinfunction "PDR_ON_143") (pintype "passive"))
    )
    (net (code "58") (name "Net-(U4-PH0-OSC_IN)") (class "Default")
      (node (ref "C28") (pin "2") (pinfunction "2_2") (pintype "passive"))
      (node (ref "R12") (pin "2") (pinfunction "2_2") (pintype "passive"))
      (node (ref "U4") (pin "23") (pinfunction "PH0-OSC_IN_23") (pintype "passive"))
      (node (ref "Y2") (pin "2") (pinfunction "OSC2_2") (pintype "passive"))
    )
    (net (code "59") (name "Net-(U4-PH1-OSC_OUT)") (class "Default")
      (node (ref "C27") (pin "2") (pinfunction "2_2") (pintype "passive"))
      (node (ref "R12") (pin "1") (pinfunction "1_1") (pintype "passive"))
      (node (ref "U4") (pin "24") (pinfunction "PH1-OSC_OUT_24") (pintype "passive"))
      (node (ref "Y2") (pin "1") (pinfunction "OSC1_1") (pintype "passive"))
    )
    (net (code "60") (name "Net-(U4-Vcap_1)") (class "Default")
      (node (ref "C29") (pin "1") (pinfunction "1_1") (pintype "passive"))
      (node (ref "U4") (pin "71") (pinfunction "Vcap_1_71") (pintype "passive"))
    )
    (net (code "61") (name "Net-(U4-Vcap_2)") (class "Default")
      (node (ref "C31") (pin "1") (pinfunction "1_1") (pintype "passive"))
      (node (ref "U4") (pin "106") (pinfunction "Vcap_2_106") (pintype "passive"))
    )
    (net (code "62") (name "VCC3.3M") (class "Default")
      (node (ref "C11") (pin "2") (pinfunction "2_2") (pintype "passive"))
      (node (ref "C13") (pin "1") (pinfunction "1_1") (pintype "passive"))
      (node (ref "C14") (pin "1") (pinfunction "1_1") (pintype "passive"))
      (node (ref "C15") (pin "1") (pinfunction "1_1") (pintype "passive"))
      (node (ref "C16") (pin "1") (pinfunction "1_1") (pintype "passive"))
      (node (ref "C17") (pin "1") (pinfunction "1_1") (pintype "passive"))
      (node (ref "C18") (pin "1") (pinfunction "1_1") (pintype "passive"))
      (node (ref "C19") (pin "1") (pinfunction "1_1") (pintype "passive"))
      (node (ref "C20") (pin "1") (pinfunction "1_1") (pintype "passive"))
      (node (ref "C21") (pin "1") (pinfunction "1_1") (pintype "passive"))
      (node (ref "C22") (pin "1") (pinfunction "1_1") (pintype "passive"))
      (node (ref "C23") (pin "1") (pinfunction "1_1") (pintype "passive"))
      (node (ref "C24") (pin "1") (pinfunction "1_1") (pintype "passive"))
      (node (ref "C34") (pin "1") (pinfunction "1_1") (pintype "passive"))
      (node (ref "P2") (pin "1") (pinfunction "1_1") (pintype "passive"))
      (node (ref "P2") (pin "2") (pinfunction "2_2") (pintype "passive"))
      (node (ref "R14") (pin "2") (pinfunction "2_2") (pintype "passive"))
      (node (ref "R16") (pin "2") (pinfunction "2_2") (pintype "passive"))
      (node (ref "R3") (pin "2") (pinfunction "2_2") (pintype "passive"))
      (node (ref "R5") (pin "2") (pinfunction "2_2") (pintype "passive"))
      (node (ref "R8") (pin "1") (pinfunction "1_1") (pintype "passive"))
      (node (ref "Remote") (pin "3") (pinfunction "3_3") (pintype "passive"))
      (node (ref "STLINK") (pin "4") (pinfunction "4_4") (pintype "passive"))
      (node (ref "U4") (pin "108") (pinfunction "VDD_108") (pintype "passive"))
      (node (ref "U4") (pin "121") (pinfunction "VDD_121") (pintype "passive"))
      (node (ref "U4") (pin "131") (pinfunction "VDD_131") (pintype "passive"))
      (node (ref "U4") (pin "144") (pinfunction "VDD_144") (pintype "passive"))
      (node (ref "U4") (pin "17") (pinfunction "VDD_17") (pintype "passive"))
      (node (ref "U4") (pin "30") (pinfunction "VDD_30") (pintype "passive"))
      (node (ref "U4") (pin "39") (pinfunction "VDD_39") (pintype "passive"))
      (node (ref "U4") (pin "52") (pinfunction "VDD_52") (pintype "passive"))
      (node (ref "U4") (pin "6") (pinfunction "VBAT_6") (pintype "passive"))
      (node (ref "U4") (pin "62") (pinfunction "VDD_62") (pintype "passive"))
      (node (ref "U4") (pin "72") (pinfunction "VDD_72") (pintype "passive"))
      (node (ref "U4") (pin "84") (pinfunction "VDD_84") (pintype "passive"))
      (node (ref "U4") (pin "95") (pinfunction "VDD_95") (pintype "passive"))
    )
    (net (code "63") (name "unconnected-(U1-n.c.-Pad5)") (class "Default")
      (node (ref "U1") (pin "5") (pinfunction "n.c._5") (pintype "passive+no_connect"))
    )
    (net (code "64") (name "unconnected-(U3-CTS#-Pad5)") (class "Default")
      (node (ref "U3") (pin "5") (pinfunction "CTS#_5") (pintype "passive+no_connect"))
    )
    (net (code "65") (name "unconnected-(U3-RTS#-Pad4)") (class "Default")
      (node (ref "U3") (pin "4") (pinfunction "RTS#_4") (pintype "passive+no_connect"))
    )
    (net (code "66") (name "unconnected-(U3-TNOW-Pad6)") (class "Default")
      (node (ref "U3") (pin "6") (pinfunction "TNOW_6") (pintype "passive+no_connect"))
    )
    (net (code "67") (name "unconnected-(U4-PA0-WKUP{slash}U2_CTS{slash}U4_TX{slash}ETH_MII_CRS{slash}TIM2_CH1_ETR{slash}TIM5_CH1{slash}TIM8_ETR{slash}ADC123_IN0-Pad34)") (class "Default")
      (node (ref "U4") (pin "34") (pinfunction "PA0-WKUP/U2_CTS/U4_TX/ETH_MII_CRS/TIM2_CH1_ETR/TIM5_CH1/TIM8_ETR/ADC123_IN0_34") (pintype "passive"))
    )
    (net (code "68") (name "unconnected-(U4-PA1{slash}U2_RTS{slash}U4_RX{slash}ETH_RMII_REF_CLK{slash}ETH_MII_RX_CLK{slash}TIM2_CH2{slash}TIM5_CH2{slash}ADC123_IN1-Pad35)") (class "Default")
      (node (ref "U4") (pin "35") (pinfunction "PA1/U2_RTS/U4_RX/ETH_RMII_REF_CLK/ETH_MII_RX_CLK/TIM2_CH2/TIM5_CH2/ADC123_IN1_35") (pintype "passive"))
    )
    (net (code "69") (name "unconnected-(U4-PA6{slash}SPI1_MISO{slash}TIM1_BKIN{slash}TIM3_CH1{slash}TIM8_BKIN{slash}TIM13_CH1{slash}DCMI_PIXCLK{slash}ADC12_IN6-Pad42)") (class "Default")
      (node (ref "U4") (pin "42") (pinfunction "PA6/SPI1_MISO/TIM1_BKIN/TIM3_CH1/TIM8_BKIN/TIM13_CH1/DCMI_PIXCLK/ADC12_IN6_42") (pintype "passive"))
    )
    (net (code "70") (name "unconnected-(U4-PA7{slash}SPI1_MOSI{slash}TIM1_CH1N{slash}TIM3_CH2{slash}TIM8_CH1N{slash}TIM14_CH1{slash}ETH_MII_RX_DV{slash}ETH_RMII_CRS_DV{slash}ADC12_IN7-Pad43)") (class "Default")
      (node (ref "U4") (pin "43") (pinfunction "PA7/SPI1_MOSI/TIM1_CH1N/TIM3_CH2/TIM8_CH1N/TIM14_CH1/ETH_MII_RX_DV/ETH_RMII_CRS_DV/ADC12_IN7_43") (pintype "passive"))
    )
    (net (code "71") (name "unconnected-(U4-PA15{slash}JTDI{slash}SPI1_NSS{slash}SPI3_NSS{slash}TIM2_CH1_ETR{slash}I2S3_WS-Pad110)") (class "Default")
      (node (ref "U4") (pin "110") (pinfunction "PA15/JTDI/SPI1_NSS/SPI3_NSS/TIM2_CH1_ETR/I2S3_WS_110") (pintype "passive"))
    )
    (net (code "72") (name "unconnected-(U4-PB0{slash}TIM1_CH2N{slash}TIM3_CH3{slash}TIM8_CH2N{slash}OTG_HS_ULPI_D1{slash}ETH_MII_RXD2{slash}ADC12_IN8-Pad46)") (class "Default")
      (node (ref "U4") (pin "46") (pinfunction "PB0/TIM1_CH2N/TIM3_CH3/TIM8_CH2N/OTG_HS_ULPI_D1/ETH_MII_RXD2/ADC12_IN8_46") (pintype "passive"))
    )
    (net (code "73") (name "unconnected-(U4-PB1{slash}TIM1_CH3N{slash}TIM3_CH4{slash}TIM8_CH3N{slash}OTG_HS_INTN{slash}ETH_MII_RXD3{slash}ADC12_IN9-Pad47)") (class "Default")
      (node (ref "U4") (pin "47") (pinfunction "PB1/TIM1_CH3N/TIM3_CH4/TIM8_CH3N/OTG_HS_INTN/ETH_MII_RXD3/ADC12_IN9_47") (pintype "passive"))
    )
    (net (code "74") (name "unconnected-(U4-PB3{slash}JTDO{slash}TRACESWO{slash}TIM2_CH2{slash}SPI1_SCK{slash}SPI3_SCK{slash}I2S3_CK-Pad133)") (class "Default")
      (node (ref "U4") (pin "133") (pinfunction "PB3/JTDO/TRACESWO/TIM2_CH2/SPI1_SCK/SPI3_SCK/I2S3_CK_133") (pintype "passive"))
    )
    (net (code "75") (name "unconnected-(U4-PB4{slash}JNTRST{slash}TIM3_CH1{slash}SPI1_MISO{slash}SPI3_MISO{slash}I2S3ext_SD-Pad134)") (class "Default")
      (node (ref "U4") (pin "134") (pinfunction "PB4/JNTRST/TIM3_CH1/SPI1_MISO/SPI3_MISO/I2S3ext_SD_134") (pintype "passive"))
    )
    (net (code "76") (name "unconnected-(U4-PB5{slash}TIM3_CH2{slash}SPI1_MOSI{slash}SPI3_MOSI{slash}CAN2_RX{slash}I2C1_SMBA{slash}OTG_HS_ULPI_D7{slash}ETH_PPS_OUT{slash}DCMI_D10{slash}I2S3_SD-Pad135)") (class "Default")
      (node (ref "U4") (pin "135") (pinfunction "PB5/TIM3_CH2/SPI1_MOSI/SPI3_MOSI/CAN2_RX/I2C1_SMBA/OTG_HS_ULPI_D7/ETH_PPS_OUT/DCMI_D10/I2S3_SD_135") (pintype "passive"))
    )
    (net (code "77") (name "unconnected-(U4-PB12{slash}SPI2_NSS{slash}TIM1_BKIN{slash}U3_CK{slash}CAN2_RX{slash}I2C2_SMBA{slash}OTG_HS_ULPI_D5{slash}OTG_HS_ID{slash}ETH_MII_TXD0{slash}ETH_RMII_TXD0{slash}I2S2_WS-Pad73)") (class "Default")
      (node (ref "U4") (pin "73") (pinfunction "PB12/SPI2_NSS/TIM1_BKIN/U3_CK/CAN2_RX/I2C2_SMBA/OTG_HS_ULPI_D5/OTG_HS_ID/ETH_MII_TXD0/ETH_RMII_TXD0/I2S2_WS_73") (pintype "passive"))
    )
    (net (code "78") (name "unconnected-(U4-PB13{slash}SPI2_SCK{slash}TIM1_CH1N{slash}U3_CTS{slash}CAN2_TX{slash}OTG_HS_ULPI_D6{slash}OTG_HS_VBUS{slash}ETH_MII_TXD1{slash}ETH_RMII_TXD1{slash}I2S2_CK-Pad74)") (class "Default")
      (node (ref "U4") (pin "74") (pinfunction "PB13/SPI2_SCK/TIM1_CH1N/U3_CTS/CAN2_TX/OTG_HS_ULPI_D6/OTG_HS_VBUS/ETH_MII_TXD1/ETH_RMII_TXD1/I2S2_CK_74") (pintype "passive"))
    )
    (net (code "79") (name "unconnected-(U4-PB14{slash}SPI2_MISO{slash}TIM1_CH2N{slash}TIM8_CH2N{slash}TIM12_CH1{slash}U3_RTS{slash}OTG_HS_DM{slash}I2S2ext_SD-Pad75)") (class "Default")
      (node (ref "U4") (pin "75") (pinfunction "PB14/SPI2_MISO/TIM1_CH2N/TIM8_CH2N/TIM12_CH1/U3_RTS/OTG_HS_DM/I2S2ext_SD_75") (pintype "passive"))
    )
    (net (code "80") (name "unconnected-(U4-PB15{slash}SPI2_MOSI{slash}TIM1_CH3N{slash}TIM8_CH3N{slash}TIM12_CH2{slash}OTG_HS_DP{slash}I2S2_SD-Pad76)") (class "Default")
      (node (ref "U4") (pin "76") (pinfunction "PB15/SPI2_MOSI/TIM1_CH3N/TIM8_CH3N/TIM12_CH2/OTG_HS_DP/I2S2_SD_76") (pintype "passive"))
    )
    (net (code "81") (name "unconnected-(U4-PC1{slash}ETH_MDC{slash}ADC123_IN11-Pad27)") (class "Default")
      (node (ref "U4") (pin "27") (pinfunction "PC1/ETH_MDC/ADC123_IN11_27") (pintype "passive"))
    )
    (net (code "82") (name "unconnected-(U4-PC2{slash}SPI2_MISO{slash}OTG_HS_ULPI_DIR{slash}ETH_MII_TXD2{slash}I2S2ext_SD{slash}ADC123_IN12-Pad28)") (class "Default")
      (node (ref "U4") (pin "28") (pinfunction "PC2/SPI2_MISO/OTG_HS_ULPI_DIR/ETH_MII_TXD2/I2S2ext_SD/ADC123_IN12_28") (pintype "passive"))
    )
    (net (code "83") (name "unconnected-(U4-PC3{slash}SPI2_MOSI{slash}OTG_HS_ULPI_NXT{slash}ETH_MII_TX_CLK{slash}I2S2_SD{slash}ADC123_IN13-Pad29)") (class "Default")
      (node (ref "U4") (pin "29") (pinfunction "PC3/SPI2_MOSI/OTG_HS_ULPI_NXT/ETH_MII_TX_CLK/I2S2_SD/ADC123_IN13_29") (pintype "passive"))
    )
    (net (code "84") (name "unconnected-(U4-PC4{slash}ETH_MII_RXD0{slash}ETH_RMII_RXD0{slash}ADC12_IN14-Pad44)") (class "Default")
      (node (ref "U4") (pin "44") (pinfunction "PC4/ETH_MII_RXD0/ETH_RMII_RXD0/ADC12_IN14_44") (pintype "passive"))
    )
    (net (code "85") (name "unconnected-(U4-PC5{slash}ETH_MII_RXD1{slash}ETH_RMII_RXD1{slash}ADC12_IN15-Pad45)") (class "Default")
      (node (ref "U4") (pin "45") (pinfunction "PC5/ETH_MII_RXD1/ETH_RMII_RXD1/ADC12_IN15_45") (pintype "passive"))
    )
    (net (code "86") (name "unconnected-(U4-PC8{slash}TIM3_CH3{slash}TIM8_CH3{slash}U6_CK{slash}SDIO_D0{slash}DCMI_D2-Pad98)") (class "Default")
      (node (ref "U4") (pin "98") (pinfunction "PC8/TIM3_CH3/TIM8_CH3/U6_CK/SDIO_D0/DCMI_D2_98") (pintype "passive"))
    )
    (net (code "87") (name "unconnected-(U4-PC9{slash}TIM3_CH4{slash}TIM8_CH4{slash}I2C3_SDA{slash}SDIO_D1{slash}DCMI_D3{slash}MCO2{slash}I2S_CKIN-Pad99)") (class "Default")
      (node (ref "U4") (pin "99") (pinfunction "PC9/TIM3_CH4/TIM8_CH4/I2C3_SDA/SDIO_D1/DCMI_D3/MCO2/I2S_CKIN_99") (pintype "passive"))
    )
    (net (code "88") (name "unconnected-(U4-PC10{slash}SPI3_SCK{slash}U3_TX{slash}U4_TX{slash}SDIO_D2{slash}DCMI_D8{slash}I2S3_CK-Pad111)") (class "Default")
      (node (ref "U4") (pin "111") (pinfunction "PC10/SPI3_SCK/U3_TX/U4_TX/SDIO_D2/DCMI_D8/I2S3_CK_111") (pintype "passive"))
    )
    (net (code "89") (name "unconnected-(U4-PC11{slash}SPI3_MISO{slash}U3_RX{slash}U4_RX{slash}SDIO_D3{slash}DCMI_D4{slash}I2S3ext_SD-Pad112)") (class "Default")
      (node (ref "U4") (pin "112") (pinfunction "PC11/SPI3_MISO/U3_RX/U4_RX/SDIO_D3/DCMI_D4/I2S3ext_SD_112") (pintype "passive"))
    )
    (net (code "90") (name "unconnected-(U4-PC12{slash}SPI3_MOSI{slash}U3_CK{slash}U5_TX{slash}SDIO_CK{slash}DCMI_D9{slash}I2S3_SD-Pad113)") (class "Default")
      (node (ref "U4") (pin "113") (pinfunction "PC12/SPI3_MOSI/U3_CK/U5_TX/SDIO_CK/DCMI_D9/I2S3_SD_113") (pintype "passive"))
    )
    (net (code "91") (name "unconnected-(U4-PC13{slash}RTC_AF1-Pad7)") (class "Default")
      (node (ref "U4") (pin "7") (pinfunction "PC13/RTC_AF1_7") (pintype "passive"))
    )
    (net (code "92") (name "unconnected-(U4-PD0{slash}FSMC_D2{slash}CAN1_RX-Pad114)") (class "Default")
      (node (ref "U4") (pin "114") (pinfunction "PD0/FSMC_D2/CAN1_RX_114") (pintype "passive"))
    )
    (net (code "93") (name "unconnected-(U4-PD1{slash}FSMC_D3{slash}CAN1_TX-Pad115)") (class "Default")
      (node (ref "U4") (pin "115") (pinfunction "PD1/FSMC_D3/CAN1_TX_115") (pintype "passive"))
    )
    (net (code "94") (name "unconnected-(U4-PD2{slash}TIM3_ETR{slash}U5_RX{slash}SDIO_CMD{slash}DCMI_D11-Pad116)") (class "Default")
      (node (ref "U4") (pin "116") (pinfunction "PD2/TIM3_ETR/U5_RX/SDIO_CMD/DCMI_D11_116") (pintype "passive"))
    )
    (net (code "95") (name "unconnected-(U4-PD3{slash}FSMC_CLK{slash}U2_CTS-Pad117)") (class "Default")
      (node (ref "U4") (pin "117") (pinfunction "PD3/FSMC_CLK/U2_CTS_117") (pintype "passive"))
    )
    (net (code "96") (name "unconnected-(U4-PD4{slash}FSMC_NOE{slash}U2_RTS-Pad118)") (class "Default")
      (node (ref "U4") (pin "118") (pinfunction "PD4/FSMC_NOE/U2_RTS_118") (pintype "passive"))
    )
    (net (code "97") (name "unconnected-(U4-PD5{slash}FSMC_NWE{slash}U2_TX-Pad119)") (class "Default")
      (node (ref "U4") (pin "119") (pinfunction "PD5/FSMC_NWE/U2_TX_119") (pintype "passive"))
    )
    (net (code "98") (name "unconnected-(U4-PD6{slash}FSMC_NWAIT{slash}U2_RX-Pad122)") (class "Default")
      (node (ref "U4") (pin "122") (pinfunction "PD6/FSMC_NWAIT/U2_RX_122") (pintype "passive"))
    )
    (net (code "99") (name "unconnected-(U4-PD7{slash}FSMC_NE1{slash}FSMC_NCE2{slash}U2_CK-Pad123)") (class "Default")
      (node (ref "U4") (pin "123") (pinfunction "PD7/FSMC_NE1/FSMC_NCE2/U2_CK_123") (pintype "passive"))
    )
    (net (code "100") (name "unconnected-(U4-PD8{slash}FSMC_D13{slash}U3_TX-Pad77)") (class "Default")
      (node (ref "U4") (pin "77") (pinfunction "PD8/FSMC_D13/U3_TX_77") (pintype "passive"))
    )
    (net (code "101") (name "unconnected-(U4-PD9{slash}FSMC_D14{slash}U3_RX-Pad78)") (class "Default")
      (node (ref "U4") (pin "78") (pinfunction "PD9/FSMC_D14/U3_RX_78") (pintype "passive"))
    )
    (net (code "102") (name "unconnected-(U4-PD10{slash}FSMC_D15{slash}U3_CK-Pad79)") (class "Default")
      (node (ref "U4") (pin "79") (pinfunction "PD10/FSMC_D15/U3_CK_79") (pintype "passive"))
    )
    (net (code "103") (name "unconnected-(U4-PD11{slash}FSMC_A16{slash}FSMC_CLE{slash}U3_CTS-Pad80)") (class "Default")
      (node (ref "U4") (pin "80") (pinfunction "PD11/FSMC_A16/FSMC_CLE/U3_CTS_80") (pintype "passive"))
    )
    (net (code "104") (name "unconnected-(U4-PD12{slash}FSMC_A17{slash}FSMC_ALE{slash}TIM4_CH1{slash}U3_RTS-Pad81)") (class "Default")
      (node (ref "U4") (pin "81") (pinfunction "PD12/FSMC_A17/FSMC_ALE/TIM4_CH1/U3_RTS_81") (pintype "passive"))
    )
    (net (code "105") (name "unconnected-(U4-PD13{slash}FSMC_A18{slash}TIM4_CH2-Pad82)") (class "Default")
      (node (ref "U4") (pin "82") (pinfunction "PD13/FSMC_A18/TIM4_CH2_82") (pintype "passive"))
    )
    (net (code "106") (name "unconnected-(U4-PD14{slash}FSMC_D0{slash}TIM4_CH3-Pad85)") (class "Default")
      (node (ref "U4") (pin "85") (pinfunction "PD14/FSMC_D0/TIM4_CH3_85") (pintype "passive"))
    )
    (net (code "107") (name "unconnected-(U4-PD15{slash}FSMC_D1{slash}TIM4_CH4-Pad86)") (class "Default")
      (node (ref "U4") (pin "86") (pinfunction "PD15/FSMC_D1/TIM4_CH4_86") (pintype "passive"))
    )
    (net (code "108") (name "unconnected-(U4-PE1{slash}FSMC_NBL1{slash}DCMI_D3-Pad142)") (class "Default")
      (node (ref "U4") (pin "142") (pinfunction "PE1/FSMC_NBL1/DCMI_D3_142") (pintype "passive"))
    )
    (net (code "109") (name "unconnected-(U4-PE2{slash}TRACECLK{slash}FSMC_A23{slash}ETH_MII_TXD3-Pad1)") (class "Default")
      (node (ref "U4") (pin "1") (pinfunction "PE2/TRACECLK/FSMC_A23/ETH_MII_TXD3_1") (pintype "passive"))
    )
    (net (code "110") (name "unconnected-(U4-PE3{slash}TRACED0{slash}FSMC_A19-Pad2)") (class "Default")
      (node (ref "U4") (pin "2") (pinfunction "PE3/TRACED0/FSMC_A19_2") (pintype "passive"))
    )
    (net (code "111") (name "unconnected-(U4-PE4{slash}TRACED1{slash}FSMC_A20{slash}DCMI_D4-Pad3)") (class "Default")
      (node (ref "U4") (pin "3") (pinfunction "PE4/TRACED1/FSMC_A20/DCMI_D4_3") (pintype "passive"))
    )
    (net (code "112") (name "unconnected-(U4-PE5{slash}TRACED2{slash}FSMC_A21{slash}TIM9_CH1{slash}DCMI_D6-Pad4)") (class "Default")
      (node (ref "U4") (pin "4") (pinfunction "PE5/TRACED2/FSMC_A21/TIM9_CH1/DCMI_D6_4") (pintype "passive"))
    )
    (net (code "113") (name "unconnected-(U4-PE6{slash}TRACED3{slash}FSMC_A22{slash}TIM9_CH2{slash}DCMI_D7-Pad5)") (class "Default")
      (node (ref "U4") (pin "5") (pinfunction "PE6/TRACED3/FSMC_A22/TIM9_CH2/DCMI_D7_5") (pintype "passive"))
    )
    (net (code "114") (name "unconnected-(U4-PE7{slash}FSMC_D4{slash}TIM1_ETR-Pad58)") (class "Default")
      (node (ref "U4") (pin "58") (pinfunction "PE7/FSMC_D4/TIM1_ETR_58") (pintype "passive"))
    )
    (net (code "115") (name "unconnected-(U4-PE8{slash}FSMC_D5{slash}TIM1_CH1N-Pad59)") (class "Default")
      (node (ref "U4") (pin "59") (pinfunction "PE8/FSMC_D5/TIM1_CH1N_59") (pintype "passive"))
    )
    (net (code "116") (name "unconnected-(U4-PE9{slash}FSMC_D6{slash}TIM1_CH1-Pad60)") (class "Default")
      (node (ref "U4") (pin "60") (pinfunction "PE9/FSMC_D6/TIM1_CH1_60") (pintype "passive"))
    )
    (net (code "117") (name "unconnected-(U4-PE10{slash}FSMC_D7{slash}TIM1_CH2N-Pad63)") (class "Default")
      (node (ref "U4") (pin "63") (pinfunction "PE10/FSMC_D7/TIM1_CH2N_63") (pintype "passive"))
    )
    (net (code "118") (name "unconnected-(U4-PE11{slash}FSMC_D8{slash}TIM1_CH2-Pad64)") (class "Default")
      (node (ref "U4") (pin "64") (pinfunction "PE11/FSMC_D8/TIM1_CH2_64") (pintype "passive"))
    )
    (net (code "119") (name "unconnected-(U4-PE12{slash}FSMC_D9{slash}TIM1_CH3N-Pad65)") (class "Default")
      (node (ref "U4") (pin "65") (pinfunction "PE12/FSMC_D9/TIM1_CH3N_65") (pintype "passive"))
    )
    (net (code "120") (name "unconnected-(U4-PE13{slash}FSMC_D10{slash}TIM1_CH3-Pad66)") (class "Default")
      (node (ref "U4") (pin "66") (pinfunction "PE13/FSMC_D10/TIM1_CH3_66") (pintype "passive"))
    )
    (net (code "121") (name "unconnected-(U4-PE14{slash}FSMC_D11{slash}TIM1_CH4-Pad67)") (class "Default")
      (node (ref "U4") (pin "67") (pinfunction "PE14/FSMC_D11/TIM1_CH4_67") (pintype "passive"))
    )
    (net (code "122") (name "unconnected-(U4-PE15{slash}FSMC_D12{slash}TIM1_BKIN-Pad68)") (class "Default")
      (node (ref "U4") (pin "68") (pinfunction "PE15/FSMC_D12/TIM1_BKIN_68") (pintype "passive"))
    )
    (net (code "123") (name "unconnected-(U4-PF0{slash}FSMC_A0{slash}I2C2_SDA-Pad10)") (class "Default")
      (node (ref "U4") (pin "10") (pinfunction "PF0/FSMC_A0/I2C2_SDA_10") (pintype "passive"))
    )
    (net (code "124") (name "unconnected-(U4-PF1{slash}FSMC_A1{slash}I2C2_SCL-Pad11)") (class "Default")
      (node (ref "U4") (pin "11") (pinfunction "PF1/FSMC_A1/I2C2_SCL_11") (pintype "passive"))
    )
    (net (code "125") (name "unconnected-(U4-PF2{slash}FSMC_A2{slash}I2C2_SMBA-Pad12)") (class "Default")
      (node (ref "U4") (pin "12") (pinfunction "PF2/FSMC_A2/I2C2_SMBA_12") (pintype "passive"))
    )
    (net (code "126") (name "unconnected-(U4-PF3{slash}FSMC_A3{slash}ADC3_IN9-Pad13)") (class "Default")
      (node (ref "U4") (pin "13") (pinfunction "PF3/FSMC_A3/ADC3_IN9_13") (pintype "passive"))
    )
    (net (code "127") (name "unconnected-(U4-PF4{slash}FSMC_A4{slash}ADC3_IN14-Pad14)") (class "Default")
      (node (ref "U4") (pin "14") (pinfunction "PF4/FSMC_A4/ADC3_IN14_14") (pintype "passive"))
    )
    (net (code "128") (name "unconnected-(U4-PF5{slash}FSMC_A5{slash}ADC3_IN15-Pad15)") (class "Default")
      (node (ref "U4") (pin "15") (pinfunction "PF5/FSMC_A5/ADC3_IN15_15") (pintype "passive"))
    )
    (net (code "129") (name "unconnected-(U4-PF7{slash}TIM11_CH1{slash}FSMC_NREG{slash}ADC3_IN5-Pad19)") (class "Default")
      (node (ref "U4") (pin "19") (pinfunction "PF7/TIM11_CH1/FSMC_NREG/ADC3_IN5_19") (pintype "passive"))
    )
    (net (code "130") (name "unconnected-(U4-PF8{slash}TIM13_CH1{slash}FSMC_NIOWR{slash}ADC3_IN6-Pad20)") (class "Default")
      (node (ref "U4") (pin "20") (pinfunction "PF8/TIM13_CH1/FSMC_NIOWR/ADC3_IN6_20") (pintype "passive"))
    )
    (net (code "131") (name "unconnected-(U4-PF11{slash}DCMI_D12-Pad49)") (class "Default")
      (node (ref "U4") (pin "49") (pinfunction "PF11/DCMI_D12_49") (pintype "passive"))
    )
    (net (code "132") (name "unconnected-(U4-PF12{slash}FSMC_A6-Pad50)") (class "Default")
      (node (ref "U4") (pin "50") (pinfunction "PF12/FSMC_A6_50") (pintype "passive"))
    )
    (net (code "133") (name "unconnected-(U4-PF13{slash}FSMC_A7-Pad53)") (class "Default")
      (node (ref "U4") (pin "53") (pinfunction "PF13/FSMC_A7_53") (pintype "passive"))
    )
    (net (code "134") (name "unconnected-(U4-PF14{slash}FSMC_A8-Pad54)") (class "Default")
      (node (ref "U4") (pin "54") (pinfunction "PF14/FSMC_A8_54") (pintype "passive"))
    )
    (net (code "135") (name "unconnected-(U4-PF15{slash}FSMC_A9-Pad55)") (class "Default")
      (node (ref "U4") (pin "55") (pinfunction "PF15/FSMC_A9_55") (pintype "passive"))
    )
    (net (code "136") (name "unconnected-(U4-PG0{slash}FSMC_A10-Pad56)") (class "Default")
      (node (ref "U4") (pin "56") (pinfunction "PG0/FSMC_A10_56") (pintype "passive"))
    )
    (net (code "137") (name "unconnected-(U4-PG1{slash}FSMC_A11-Pad57)") (class "Default")
      (node (ref "U4") (pin "57") (pinfunction "PG1/FSMC_A11_57") (pintype "passive"))
    )
    (net (code "138") (name "unconnected-(U4-PG2{slash}FSMC_A12-Pad87)") (class "Default")
      (node (ref "U4") (pin "87") (pinfunction "PG2/FSMC_A12_87") (pintype "passive"))
    )
    (net (code "139") (name "unconnected-(U4-PG3{slash}FSMC_A13-Pad88)") (class "Default")
      (node (ref "U4") (pin "88") (pinfunction "PG3/FSMC_A13_88") (pintype "passive"))
    )
    (net (code "140") (name "unconnected-(U4-PG4{slash}FSMC_A14-Pad89)") (class "Default")
      (node (ref "U4") (pin "89") (pinfunction "PG4/FSMC_A14_89") (pintype "passive"))
    )
    (net (code "141") (name "unconnected-(U4-PG5{slash}FSMC_A15-Pad90)") (class "Default")
      (node (ref "U4") (pin "90") (pinfunction "PG5/FSMC_A15_90") (pintype "passive"))
    )
    (net (code "142") (name "unconnected-(U4-PG6{slash}FSMC_INT2-Pad91)") (class "Default")
      (node (ref "U4") (pin "91") (pinfunction "PG6/FSMC_INT2_91") (pintype "passive"))
    )
    (net (code "143") (name "unconnected-(U4-PG7{slash}FSMC_INT3{slash}U6_CK-Pad92)") (class "Default")
      (node (ref "U4") (pin "92") (pinfunction "PG7/FSMC_INT3/U6_CK_92") (pintype "passive"))
    )
    (net (code "144") (name "unconnected-(U4-PG8{slash}U6_RTS{slash}ETH_PPS_OUT-Pad93)") (class "Default")
      (node (ref "U4") (pin "93") (pinfunction "PG8/U6_RTS/ETH_PPS_OUT_93") (pintype "passive"))
    )
    (net (code "145") (name "unconnected-(U4-PG9{slash}FSMC_NE2{slash}FSMC_NCE3{slash}U6_RX-Pad124)") (class "Default")
      (node (ref "U4") (pin "124") (pinfunction "PG9/FSMC_NE2/FSMC_NCE3/U6_RX_124") (pintype "passive"))
    )
    (net (code "146") (name "unconnected-(U4-PG10{slash}FSMC_NCE4_1{slash}FSMC_NE3-Pad125)") (class "Default")
      (node (ref "U4") (pin "125") (pinfunction "PG10/FSMC_NCE4_1/FSMC_NE3_125") (pintype "passive"))
    )
    (net (code "147") (name "unconnected-(U4-PG11{slash}FSMC_NCE4_2{slash}ETH_MII_TX_EN{slash}ETH_RMII_TX_EN-Pad126)") (class "Default")
      (node (ref "U4") (pin "126") (pinfunction "PG11/FSMC_NCE4_2/ETH_MII_TX_EN/ETH_RMII_TX_EN_126") (pintype "passive"))
    )
    (net (code "148") (name "unconnected-(U4-PG12{slash}FSMC_NE4{slash}U6_RTS-Pad127)") (class "Default")
      (node (ref "U4") (pin "127") (pinfunction "PG12/FSMC_NE4/U6_RTS_127") (pintype "passive"))
    )
    (net (code "149") (name "unconnected-(U4-PG13{slash}FSMC_A24{slash}U6_CTS{slash}ETH_MII_TXD0{slash}ETH_RMII_TXD0-Pad128)") (class "Default")
      (node (ref "U4") (pin "128") (pinfunction "PG13/FSMC_A24/U6_CTS/ETH_MII_TXD0/ETH_RMII_TXD0_128") (pintype "passive"))
    )
    (net (code "150") (name "unconnected-(U4-PG14{slash}FSMC_A25{slash}U6_TX{slash}ETH_MII_TXD1{slash}ETH_RMII_TXD1-Pad129)") (class "Default")
      (node (ref "U4") (pin "129") (pinfunction "PG14/FSMC_A25/U6_TX/ETH_MII_TXD1/ETH_RMII_TXD1_129") (pintype "passive"))
    )
    (net (code "151") (name "unconnected-(U4-PG15{slash}U6_CTS{slash}DCMI_D13-Pad132)") (class "Default")
      (node (ref "U4") (pin "132") (pinfunction "PG15/U6_CTS/DCMI_D13_132") (pintype "passive"))
    )
  )
)
